# COMMUNICATION.net
KiCad netlist of a schematic drawn in Altium Designer
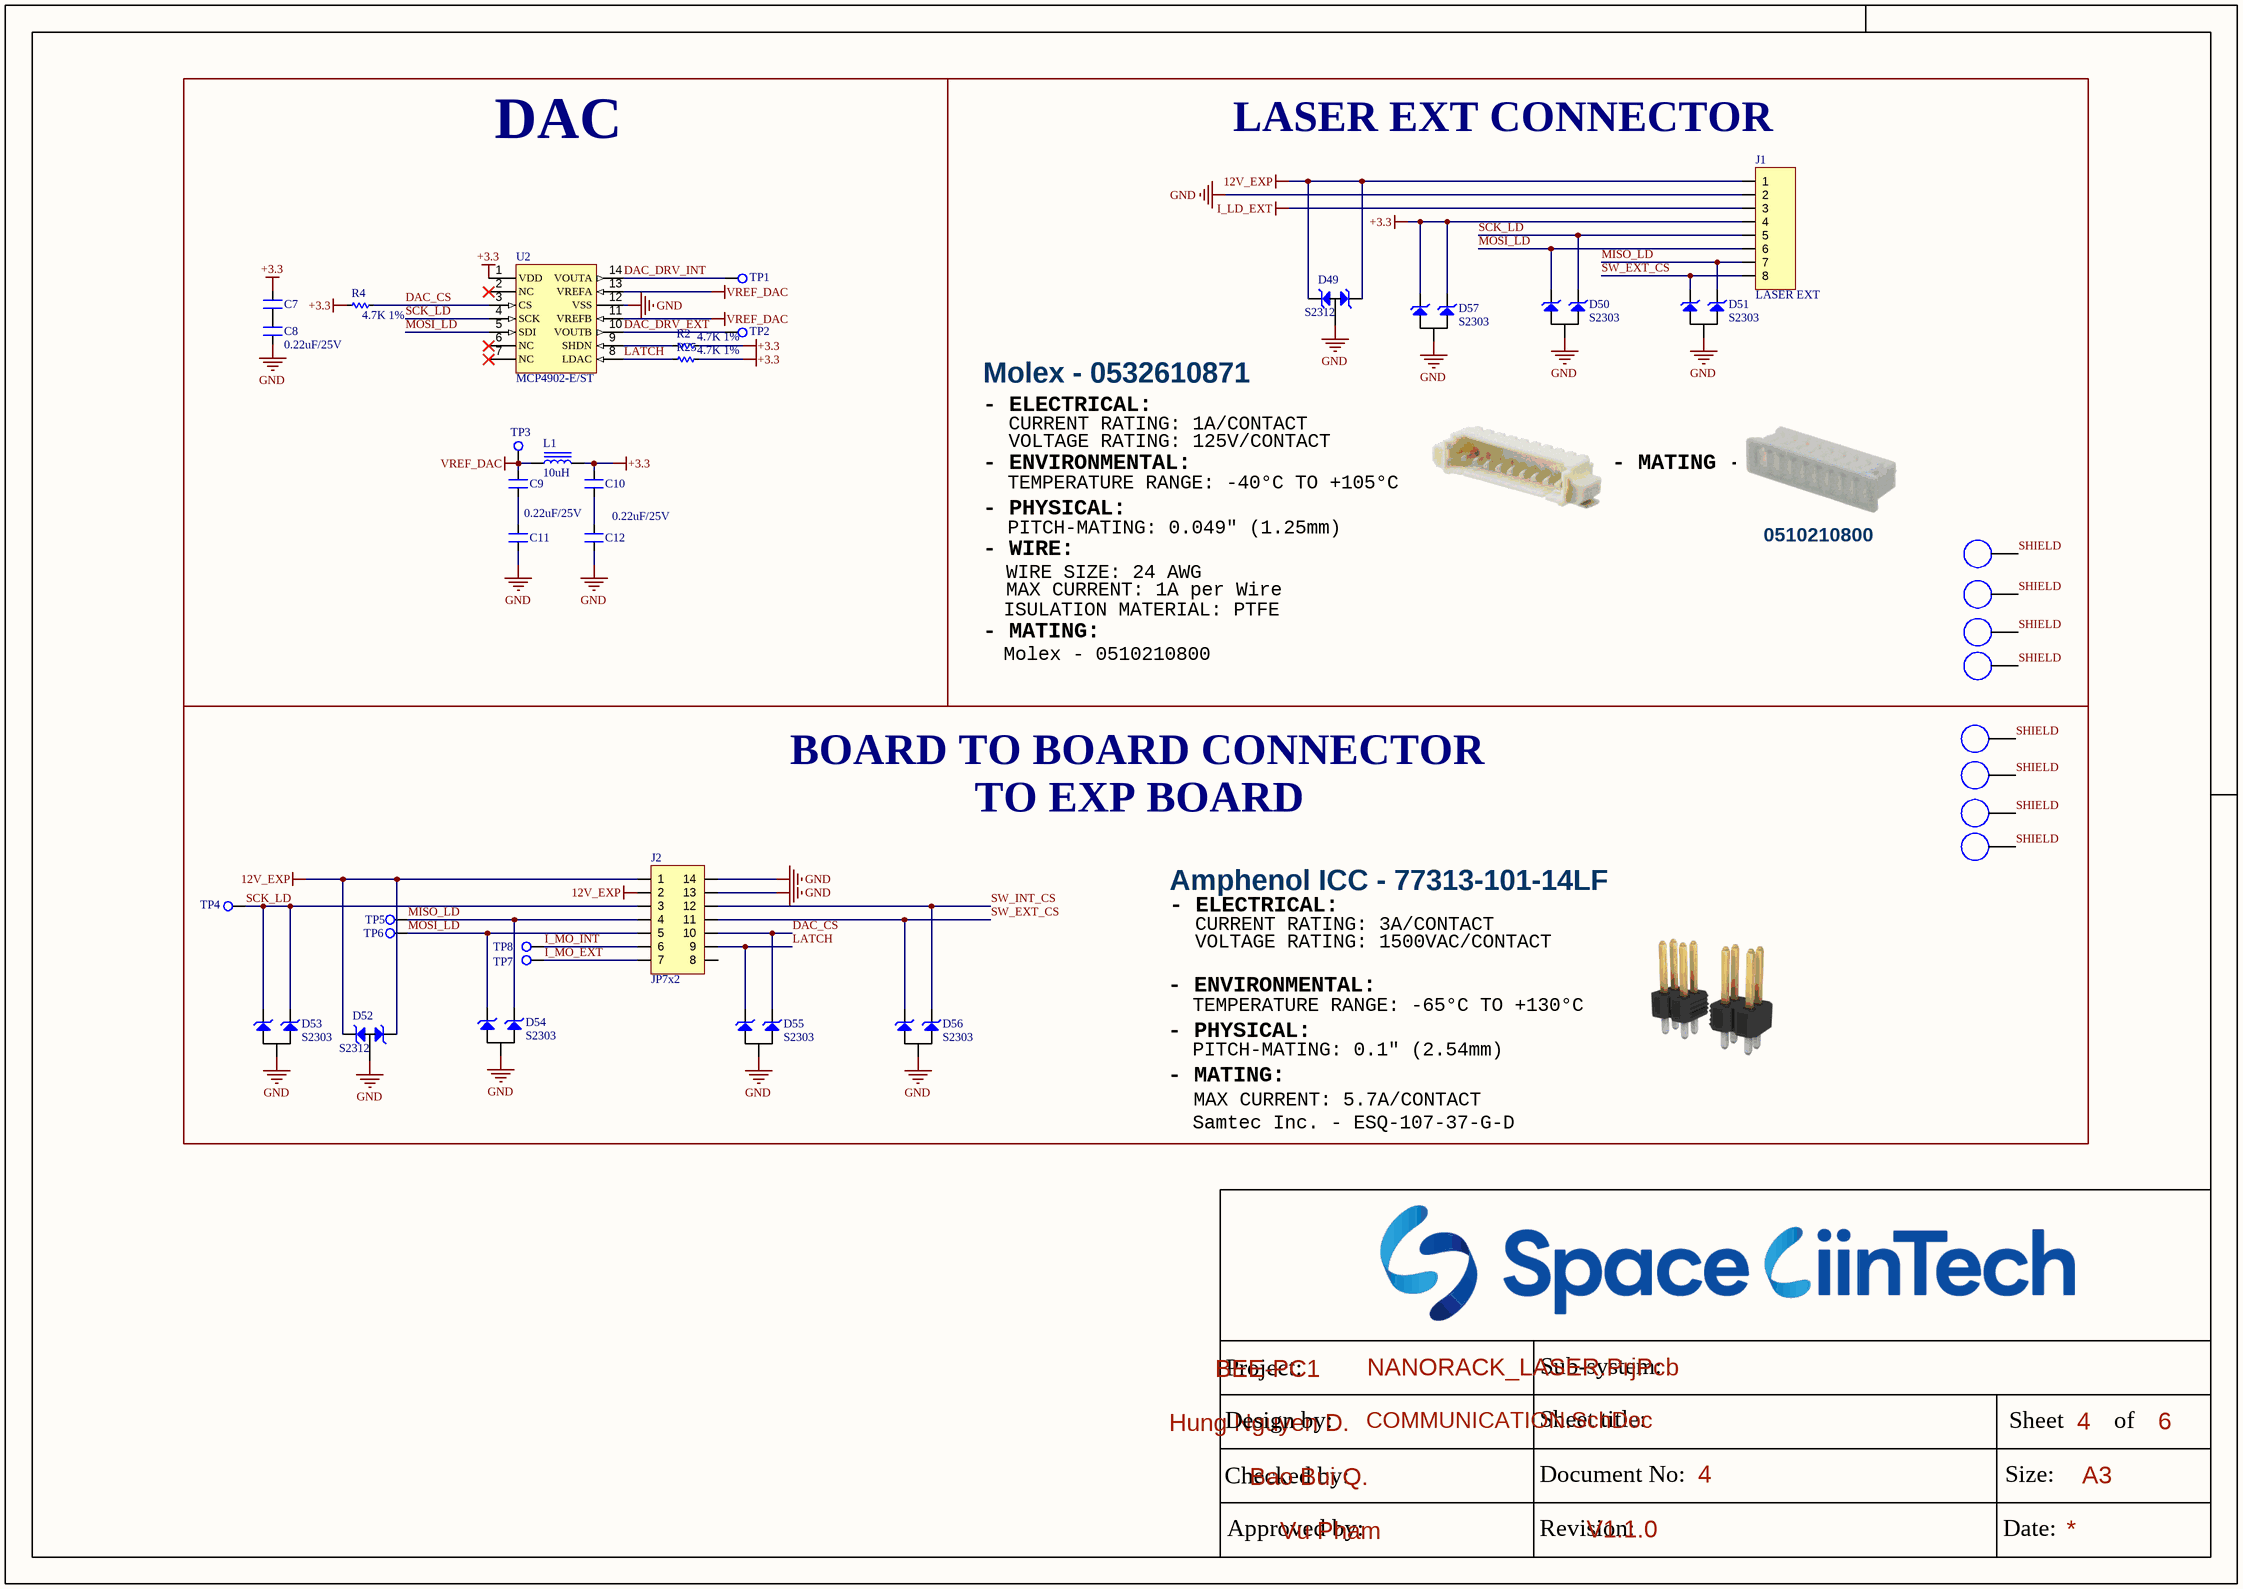
[diagram p0: COMMUNICATION.SchDoc]

(export (version "E")
  (design (tool "Eeschema 10.0.6"))
  (components
    (comp (ref "C7")
      (value "0.22uF/25V")
      (footprint "SM-0603")
      (description "0603")
      (libsource (lib "Capacitors") (part "CM"))
    )
    (comp (ref "C8")
      (value "0.22uF/25V")
      (footprint "SM-0603")
      (description "0603")
      (libsource (lib "Capacitors") (part "CM"))
    )
    (comp (ref "C9")
      (value "0.22uF/25V")
      (footprint "SM-0603")
      (description "0603")
      (libsource (lib "Capacitors") (part "CM"))
    )
    (comp (ref "C10")
      (value "0.22uF/25V")
      (footprint "SM-0603")
      (description "0603")
      (libsource (lib "Capacitors") (part "CM"))
    )
    (comp (ref "C11")
      (value "0.22uF/25V")
      (footprint "SM-0603")
      (description "0603")
      (libsource (lib "Capacitors") (part "CM"))
    )
    (comp (ref "C12")
      (value "0.22uF/25V")
      (footprint "SM-0603")
      (description "0603")
      (libsource (lib "Capacitors") (part "CM"))
    )
    (comp (ref "D49")
      (value "S2312")
      (footprint "SOT23-123")
      (description "TVS DIODE 12VWM 19VC SOT23, P/N:  S2312")
      (libsource (lib "Library") (part "S2315"))
    )
    (comp (ref "D50")
      (value "S2303")
      (footprint "SOT23-123")
      (description "TVS DIODE 3.3VWM 8VC SOT23, P/N:  \r\nS2303")
      (libsource (lib "Library") (part "S2303"))
    )
    (comp (ref "D51")
      (value "S2303")
      (footprint "SOT23-123")
      (description "TVS DIODE 3.3VWM 8VC SOT23, P/N:  \r\nS2303")
      (libsource (lib "Library") (part "S2303"))
    )
    (comp (ref "D52")
      (value "S2312")
      (footprint "SOT23-123")
      (description "TVS DIODE 12VWM 19VC SOT23, P/N:  S2312")
      (libsource (lib "Library") (part "S2315"))
    )
    (comp (ref "D53")
      (value "S2303")
      (footprint "SOT23-123")
      (description "TVS DIODE 3.3VWM 8VC SOT23, P/N:  \r\nS2303")
      (libsource (lib "Library") (part "S2303"))
    )
    (comp (ref "D54")
      (value "S2303")
      (footprint "SOT23-123")
      (description "TVS DIODE 3.3VWM 8VC SOT23, P/N:  \r\nS2303")
      (libsource (lib "Library") (part "S2303"))
    )
    (comp (ref "D55")
      (value "S2303")
      (footprint "SOT23-123")
      (description "TVS DIODE 3.3VWM 8VC SOT23, P/N:  \r\nS2303")
      (libsource (lib "Library") (part "S2303"))
    )
    (comp (ref "D56")
      (value "S2303")
      (footprint "SOT23-123")
      (description "TVS DIODE 3.3VWM 8VC SOT23, P/N:  \r\nS2303")
      (libsource (lib "Library") (part "S2303"))
    )
    (comp (ref "D57")
      (value "S2303")
      (footprint "SOT23-123")
      (description "TVS DIODE 3.3VWM 8VC SOT23, P/N:  \r\nS2303")
      (libsource (lib "Library") (part "S2303"))
    )
    (comp (ref "H1") (value "HOLD") (footprint "M3") (libsource (lib "Library_HUNG") (part "PAD_HOLD")))
    (comp (ref "H2") (value "HOLD") (footprint "M3") (libsource (lib "Library_HUNG") (part "PAD_HOLD")))
    (comp (ref "H3") (value "HOLD") (footprint "M3") (libsource (lib "Library_HUNG") (part "PAD_HOLD")))
    (comp (ref "H4") (value "HOLD") (footprint "M3") (libsource (lib "Library_HUNG") (part "PAD_HOLD")))
    (comp (ref "H5") (value "HOLD") (footprint "M3") (libsource (lib "Library_HUNG") (part "PAD_HOLD")))
    (comp (ref "H6") (value "HOLD") (footprint "M3") (libsource (lib "Library_HUNG") (part "PAD_HOLD")))
    (comp (ref "H7") (value "HOLD") (footprint "M3") (libsource (lib "Library_HUNG") (part "PAD_HOLD")))
    (comp (ref "H8") (value "HOLD") (footprint "M3") (libsource (lib "Library_HUNG") (part "PAD_HOLD")))
    (comp (ref "J1")
      (value "LASER EXT")
      (footprint "0532610871")
      (description "WR-PHD 2.54 mm Angled Socket Header")
      (fields
        (field (name "MANUFACTURER") "Würth Elektronik eiSos GmbH")
        (field (name "PARTNO") "613008143121")
        (field (name "CREATED BY") "Karrer Zheng")
      )
      (libsource (lib "Library_HUNG") (part "JP8"))
    )
    (comp (ref "J2")
      (value "JP7x2")
      (footprint "JP7-D2T")
      (description "WR-PHD 2.54 mm Dual Socket Header")
      (fields
        (field (name "MANUFACTURER") "Würth Elektronik eiSos GmbH")
        (field (name "PARTNO") "61301421821")
        (field (name "CREATED BY") "Karrer Zheng")
      )
      (libsource (lib "Library") (part "JP7x2"))
    )
    (comp (ref "L1")
      (value "10uH")
      (footprint "FER 0805/2012")
      (description "MLZ1608N100LT000")
      (libsource (lib "INDUCTOR") (part "Inductor"))
    )
    (comp (ref "R2")
      (value "4.7K 1%")
      (footprint "RES-SMD-0603")
      (description "0603")
      (fields
        (field (name "MANUFACTURER") "Generic Components")
        (field (name "PUBLISHER") "Altium Hobart Technology Centre")
      )
      (libsource (lib "Library") (part "Res-SMD"))
    )
    (comp (ref "R4")
      (value "4.7K 1%")
      (footprint "RES-SMD-0603")
      (description "0603")
      (fields
        (field (name "MANUFACTURER") "Generic Components")
        (field (name "PUBLISHER") "Altium Hobart Technology Centre")
      )
      (libsource (lib "Library") (part "Res-SMD"))
    )
    (comp (ref "R25")
      (value "4.7K 1%")
      (footprint "RES-SMD-0603")
      (description "0603")
      (fields
        (field (name "MANUFACTURER") "Generic Components")
        (field (name "PUBLISHER") "Altium Hobart Technology Centre")
      )
      (libsource (lib "Library") (part "Res-SMD"))
    )
    (comp (ref "TP1")
      (value "Test_Point")
      (footprint "TESTPOINT")
      (libsource (lib "Library_HUNG") (part "Test_Point"))
    )
    (comp (ref "TP2")
      (value "Test_Point")
      (footprint "TESTPOINT")
      (libsource (lib "Library_HUNG") (part "Test_Point"))
    )
    (comp (ref "TP3")
      (value "Test_Point")
      (footprint "TESTPOINT")
      (libsource (lib "Library_HUNG") (part "Test_Point"))
    )
    (comp (ref "TP4")
      (value "Test_Point")
      (footprint "TESTPOINT")
      (libsource (lib "Library_HUNG") (part "Test_Point"))
    )
    (comp (ref "TP5")
      (value "Test_Point")
      (footprint "TESTPOINT")
      (libsource (lib "Library_HUNG") (part "Test_Point"))
    )
    (comp (ref "TP6")
      (value "Test_Point")
      (footprint "TESTPOINT")
      (libsource (lib "Library_HUNG") (part "Test_Point"))
    )
    (comp (ref "TP7")
      (value "Test_Point")
      (footprint "TESTPOINT")
      (libsource (lib "Library_HUNG") (part "Test_Point"))
    )
    (comp (ref "TP8")
      (value "Test_Point")
      (footprint "TESTPOINT")
      (libsource (lib "Library_HUNG") (part "Test_Point"))
    )
    (comp (ref "U2")
      (value "MCP4902-E/ST")
      (footprint "TSSOP14")
      (description "IC DAC 8BIT V-OUT 14TSSOP")
      (libsource (lib "Library") (part "MCP4902"))
    )
  )
  (nets
    (net (code "1") (name "+3.3") (class "Default")
      (node (ref "C10") (pin "2") (pinfunction "2_2") (pintype "passive"))
      (node (ref "C7") (pin "2") (pinfunction "2_2") (pintype "passive"))
      (node (ref "D57") (pin "1") (pintype "passive"))
      (node (ref "D57") (pin "3") (pintype "passive"))
      (node (ref "J1") (pin "4") (pinfunction "4_4") (pintype "passive"))
      (node (ref "L1") (pin "2") (pinfunction "2_2") (pintype "passive"))
      (node (ref "R2") (pin "1") (pinfunction "1_1") (pintype "passive"))
      (node (ref "R25") (pin "1") (pinfunction "1_1") (pintype "passive"))
      (node (ref "R4") (pin "2") (pinfunction "2_2") (pintype "passive"))
      (node (ref "U2") (pin "1") (pinfunction "VDD_1") (pintype "power_in"))
    )
    (net (code "2") (name "/DAC_CS") (class "Default")
      (node (ref "D55") (pin "3") (pintype "passive"))
      (node (ref "J2") (pin "10") (pinfunction "10_10") (pintype "passive"))
      (node (ref "R4") (pin "1") (pinfunction "1_1") (pintype "passive"))
      (node (ref "U2") (pin "3") (pinfunction "CS_3") (pintype "input"))
    )
    (net (code "3") (name "/DAC_DRV_EXT") (class "Default")
      (node (ref "TP2") (pin "1") (pintype "power_in"))
      (node (ref "U2") (pin "10") (pinfunction "VOUTB_10") (pintype "output"))
    )
    (net (code "4") (name "/DAC_DRV_INT") (class "Default")
      (node (ref "TP1") (pin "1") (pintype "power_in"))
      (node (ref "U2") (pin "14") (pinfunction "VOUTA_14") (pintype "output"))
    )
    (net (code "5") (name "/I_MO_EXT") (class "Default")
      (node (ref "J2") (pin "7") (pinfunction "7_7") (pintype "passive"))
      (node (ref "TP7") (pin "1") (pintype "power_in"))
    )
    (net (code "6") (name "/I_MO_INT") (class "Default")
      (node (ref "J2") (pin "6") (pinfunction "6_6") (pintype "passive"))
      (node (ref "TP8") (pin "1") (pintype "power_in"))
    )
    (net (code "7") (name "/LATCH") (class "Default")
      (node (ref "D55") (pin "1") (pintype "passive"))
      (node (ref "J2") (pin "9") (pinfunction "9_9") (pintype "passive"))
      (node (ref "R25") (pin "2") (pinfunction "2_2") (pintype "passive"))
      (node (ref "U2") (pin "8") (pinfunction "LDAC_8") (pintype "input"))
    )
    (net (code "8") (name "/MISO_LD") (class "Default")
      (node (ref "D51") (pin "3") (pintype "passive"))
      (node (ref "D54") (pin "3") (pintype "passive"))
      (node (ref "J1") (pin "7") (pinfunction "7_7") (pintype "passive"))
      (node (ref "J2") (pin "4") (pinfunction "4_4") (pintype "passive"))
      (node (ref "TP5") (pin "1") (pintype "power_in"))
    )
    (net (code "9") (name "/MOSI_LD") (class "Default")
      (node (ref "D50") (pin "1") (pintype "passive"))
      (node (ref "D54") (pin "1") (pintype "passive"))
      (node (ref "J1") (pin "6") (pinfunction "6_6") (pintype "passive"))
      (node (ref "J2") (pin "5") (pinfunction "5_5") (pintype "passive"))
      (node (ref "TP6") (pin "1") (pintype "power_in"))
      (node (ref "U2") (pin "5") (pinfunction "SDI_5") (pintype "input"))
    )
    (net (code "10") (name "/SCK_LD") (class "Default")
      (node (ref "D50") (pin "3") (pintype "passive"))
      (node (ref "D53") (pin "1") (pintype "passive"))
      (node (ref "D53") (pin "3") (pintype "passive"))
      (node (ref "J1") (pin "5") (pinfunction "5_5") (pintype "passive"))
      (node (ref "J2") (pin "3") (pinfunction "3_3") (pintype "passive"))
      (node (ref "TP4") (pin "1") (pintype "power_in"))
      (node (ref "U2") (pin "4") (pinfunction "SCK_4") (pintype "input"))
    )
    (net (code "11") (name "/SHIELD") (class "Default")
      (node (ref "H1") (pin "1") (pintype "power_in"))
      (node (ref "H2") (pin "1") (pintype "power_in"))
      (node (ref "H3") (pin "1") (pintype "power_in"))
      (node (ref "H4") (pin "1") (pintype "power_in"))
      (node (ref "H5") (pin "1") (pintype "power_in"))
      (node (ref "H6") (pin "1") (pintype "power_in"))
      (node (ref "H7") (pin "1") (pintype "power_in"))
      (node (ref "H8") (pin "1") (pintype "power_in"))
    )
    (net (code "12") (name "/SW_EXT_CS") (class "Default")
      (node (ref "D51") (pin "1") (pintype "passive"))
      (node (ref "D56") (pin "1") (pintype "passive"))
      (node (ref "J1") (pin "8") (pinfunction "8_8") (pintype "passive"))
      (node (ref "J2") (pin "11") (pinfunction "11_11") (pintype "passive"))
    )
    (net (code "13") (name "/SW_INT_CS") (class "Default")
      (node (ref "D56") (pin "3") (pintype "passive"))
      (node (ref "J2") (pin "12") (pinfunction "12_12") (pintype "passive"))
    )
    (net (code "14") (name "12V_EXP") (class "Default")
      (node (ref "D49") (pin "1") (pintype "passive"))
      (node (ref "D49") (pin "3") (pintype "passive"))
      (node (ref "D52") (pin "1") (pintype "passive"))
      (node (ref "D52") (pin "3") (pintype "passive"))
      (node (ref "J1") (pin "1") (pinfunction "1_1") (pintype "passive"))
      (node (ref "J2") (pin "1") (pinfunction "1_1") (pintype "passive"))
      (node (ref "J2") (pin "2") (pinfunction "2_2") (pintype "passive"))
    )
    (net (code "15") (name "GND") (class "Default")
      (node (ref "C11") (pin "1") (pinfunction "1_1") (pintype "passive"))
      (node (ref "C12") (pin "1") (pinfunction "1_1") (pintype "passive"))
      (node (ref "C8") (pin "1") (pinfunction "1_1") (pintype "passive"))
      (node (ref "D49") (pin "2") (pintype "passive"))
      (node (ref "D50") (pin "2") (pintype "passive"))
      (node (ref "D51") (pin "2") (pintype "passive"))
      (node (ref "D52") (pin "2") (pintype "passive"))
      (node (ref "D53") (pin "2") (pintype "passive"))
      (node (ref "D54") (pin "2") (pintype "passive"))
      (node (ref "D55") (pin "2") (pintype "passive"))
      (node (ref "D56") (pin "2") (pintype "passive"))
      (node (ref "D57") (pin "2") (pintype "passive"))
      (node (ref "J1") (pin "2") (pinfunction "2_2") (pintype "passive"))
      (node (ref "J2") (pin "13") (pinfunction "13_13") (pintype "passive"))
      (node (ref "J2") (pin "14") (pinfunction "14_14") (pintype "passive"))
      (node (ref "U2") (pin "12") (pinfunction "VSS_12") (pintype "power_in"))
    )
    (net (code "16") (name "I_LD_EXT") (class "Default")
      (node (ref "J1") (pin "3") (pinfunction "3_3") (pintype "passive"))
    )
    (net (code "17") (name "Net-(C7-Pad1)") (class "Default")
      (node (ref "C7") (pin "1") (pinfunction "1_1") (pintype "passive"))
      (node (ref "C8") (pin "2") (pinfunction "2_2") (pintype "passive"))
    )
    (net (code "18") (name "Net-(C10-Pad1)") (class "Default")
      (node (ref "C10") (pin "1") (pinfunction "1_1") (pintype "passive"))
      (node (ref "C12") (pin "2") (pinfunction "2_2") (pintype "passive"))
    )
    (net (code "19") (name "Net-(C11-Pad2)") (class "Default")
      (node (ref "C11") (pin "2") (pinfunction "2_2") (pintype "passive"))
      (node (ref "C9") (pin "1") (pinfunction "1_1") (pintype "passive"))
    )
    (net (code "20") (name "Net-(U2-SHDN)") (class "Default")
      (node (ref "R2") (pin "2") (pinfunction "2_2") (pintype "passive"))
      (node (ref "U2") (pin "9") (pinfunction "SHDN_9") (pintype "input"))
    )
    (net (code "21") (name "VREF_DAC") (class "Default")
      (node (ref "C9") (pin "2") (pinfunction "2_2") (pintype "passive"))
      (node (ref "L1") (pin "1") (pinfunction "1_1") (pintype "passive"))
      (node (ref "TP3") (pin "1") (pintype "power_in"))
      (node (ref "U2") (pin "11") (pinfunction "VREFB_11") (pintype "input"))
      (node (ref "U2") (pin "13") (pinfunction "VREFA_13") (pintype "input"))
    )
    (net (code "22") (name "unconnected-(J2-Pad8)") (class "Default")
      (node (ref "J2") (pin "8") (pinfunction "8_8") (pintype "passive"))
    )
    (net (code "23") (name "unconnected-(U2-NC-Pad2)") (class "Default")
      (node (ref "U2") (pin "2") (pinfunction "NC_2") (pintype "tri_state+no_connect"))
    )
    (net (code "24") (name "unconnected-(U2-NC-Pad6)") (class "Default")
      (node (ref "U2") (pin "6") (pinfunction "NC_6") (pintype "tri_state+no_connect"))
    )
    (net (code "25") (name "unconnected-(U2-NC-Pad7)") (class "Default")
      (node (ref "U2") (pin "7") (pinfunction "NC_7") (pintype "tri_state+no_connect"))
    )
  )
)
